# SC70-5.net
KiCad netlist of a schematic drawn in EAGLE
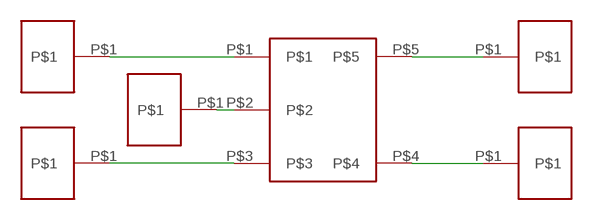
[diagram p0: schematic, sheet 1]

(export (version "E")
  (design (tool "Eeschema 10.0.6"))
  (components
    (comp (ref "U$1")
      (value "SC70-5SC70-5")
      (footprint "eagle-import:SC70-5")
      (libsource (lib "eagle-import") (part "SC70-5SC70-5"))
    )
    (comp (ref "U$2")
      (value "PAD100MIL")
      (footprint "eagle-import:100MIL_PAD")
      (libsource (lib "eagle-import") (part "PAD100MIL"))
    )
    (comp (ref "U$3")
      (value "PAD100MIL")
      (footprint "eagle-import:100MIL_PAD")
      (libsource (lib "eagle-import") (part "PAD100MIL"))
    )
    (comp (ref "U$4")
      (value "PAD100MIL")
      (footprint "eagle-import:100MIL_PAD")
      (libsource (lib "eagle-import") (part "PAD100MIL"))
    )
    (comp (ref "U$5")
      (value "PAD100MIL")
      (footprint "eagle-import:100MIL_PAD")
      (libsource (lib "eagle-import") (part "PAD100MIL"))
    )
    (comp (ref "U$6")
      (value "PAD100MIL")
      (footprint "eagle-import:100MIL_PAD")
      (libsource (lib "eagle-import") (part "PAD100MIL"))
    )
  )
  (nets
    (net (code "1") (name "Net-(U$1-PadP$1)") (class "Default")
      (node (ref "U$1") (pin "P$1") (pinfunction "P$1_P$1") (pintype "bidirectional"))
      (node (ref "U$2") (pin "P$1") (pinfunction "P$1_P$1") (pintype "bidirectional"))
    )
    (net (code "2") (name "Net-(U$1-PadP$2)") (class "Default")
      (node (ref "U$1") (pin "P$2") (pinfunction "P$2_P$2") (pintype "bidirectional"))
      (node (ref "U$3") (pin "P$1") (pinfunction "P$1_P$1") (pintype "bidirectional"))
    )
    (net (code "3") (name "Net-(U$1-PadP$3)") (class "Default")
      (node (ref "U$1") (pin "P$3") (pinfunction "P$3_P$3") (pintype "bidirectional"))
      (node (ref "U$4") (pin "P$1") (pinfunction "P$1_P$1") (pintype "bidirectional"))
    )
    (net (code "4") (name "Net-(U$1-PadP$4)") (class "Default")
      (node (ref "U$1") (pin "P$4") (pinfunction "P$4_P$4") (pintype "bidirectional"))
      (node (ref "U$5") (pin "P$1") (pinfunction "P$1_P$1") (pintype "bidirectional"))
    )
    (net (code "5") (name "Net-(U$1-PadP$5)") (class "Default")
      (node (ref "U$1") (pin "P$5") (pinfunction "P$5_P$5") (pintype "bidirectional"))
      (node (ref "U$6") (pin "P$1") (pinfunction "P$1_P$1") (pintype "bidirectional"))
    )
  )
)
